# SCH_PBFL.net
KiCad netlist of a schematic drawn in Altium Designer
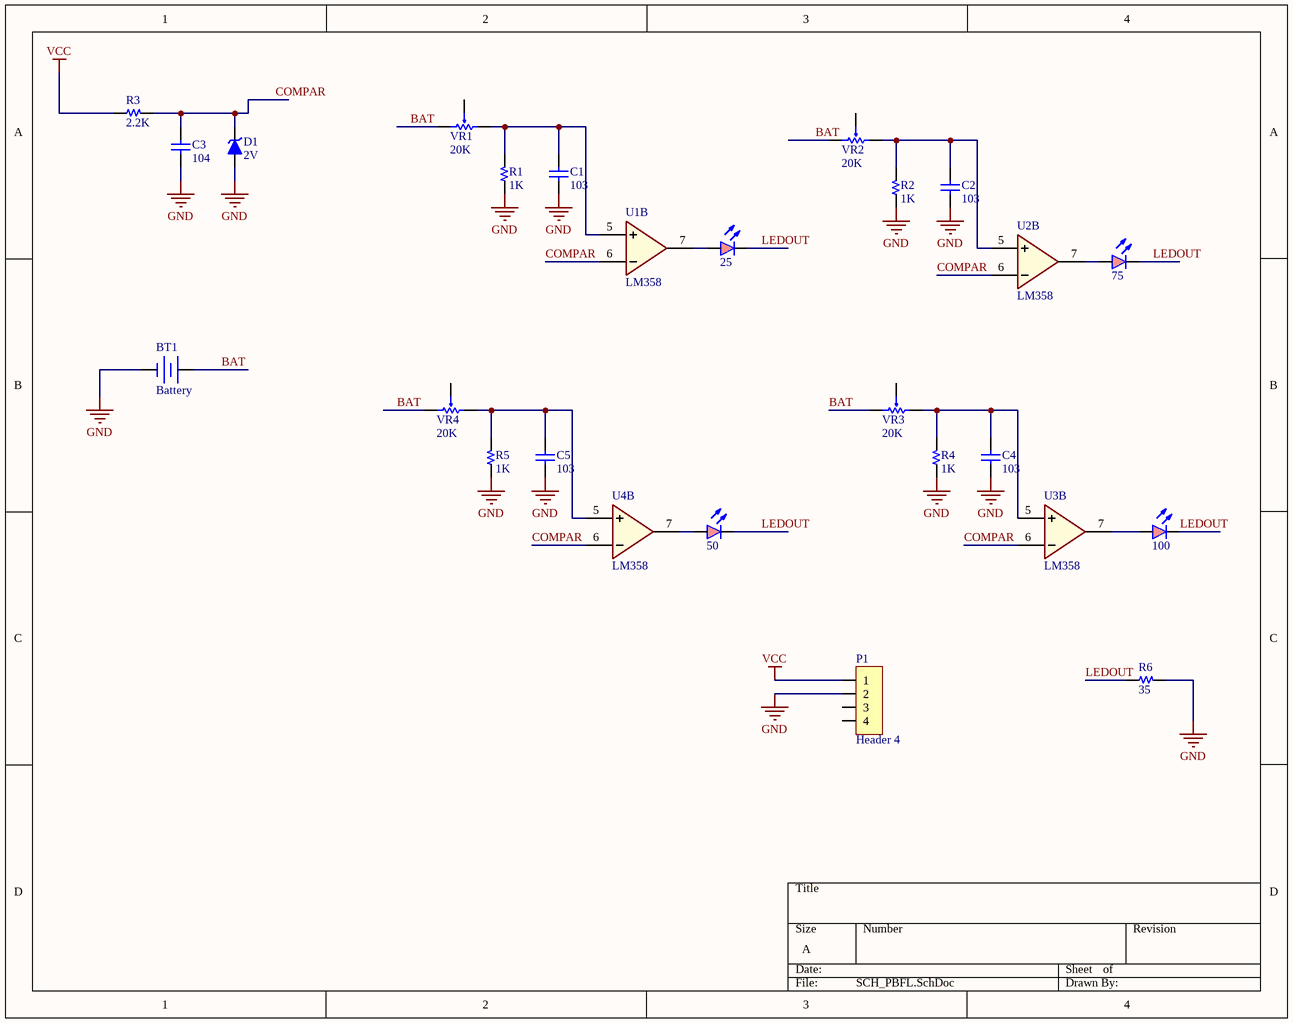
[diagram p0: SCH_PBFL.SchDoc]

(export (version "E")
  (design (tool "Eeschema 10.0.6"))
  (components
    (comp (ref "25")
      (value "LED RED")
      (footprint "LED 10MM - RED")
      (description "Typical LED 3-pin 2-color")
      (libsource (lib "led") (part "LED RED"))
    )
    (comp (ref "50")
      (value "LED RED")
      (footprint "LED 10MM - RED")
      (description "Typical LED 3-pin 2-color")
      (libsource (lib "led") (part "LED RED"))
    )
    (comp (ref "75")
      (value "LED RED")
      (footprint "LED 10MM - RED")
      (description "Typical LED 3-pin 2-color")
      (libsource (lib "led") (part "LED RED"))
    )
    (comp (ref "100")
      (value "LED RED")
      (footprint "LED 10MM - RED")
      (description "Typical LED 3-pin 2-color")
      (libsource (lib "led") (part "LED RED"))
    )
    (comp (ref "BT1")
      (value "Battery")
      (footprint "BB-BAT-18650-x1")
      (libsource (lib "chipfc_libs") (part "Battery"))
    )
    (comp (ref "C1")
      (value "103")
      (footprint "C 0805")
      (description "Capacitor non-pol")
      (libsource (lib "chipfc_libs") (part "Capacitor NP"))
    )
    (comp (ref "C2")
      (value "103")
      (footprint "C 0805")
      (description "Capacitor non-pol")
      (libsource (lib "chipfc_libs") (part "Capacitor NP"))
    )
    (comp (ref "C3")
      (value "104")
      (footprint "C 0805")
      (description "Capacitor non-pol")
      (libsource (lib "chipfc_libs") (part "Capacitor NP"))
    )
    (comp (ref "C4")
      (value "103")
      (footprint "C 0805")
      (description "Capacitor non-pol")
      (libsource (lib "chipfc_libs") (part "Capacitor NP"))
    )
    (comp (ref "C5")
      (value "103")
      (footprint "C 0805")
      (description "Capacitor non-pol")
      (libsource (lib "chipfc_libs") (part "Capacitor NP"))
    )
    (comp (ref "D1")
      (value "2V")
      (footprint "SOD123")
      (description "Zener Diode")
      (libsource (lib "chipfc_libs") (part "Diode Zener"))
    )
    (comp (ref "P1")
      (value "Header 4")
      (footprint "HDR/Header/4/BOX/RED")
      (description "Header, 4-Pin")
      (libsource (lib "connectors") (part "Header 4"))
    )
    (comp (ref "R1")
      (value "1K")
      (footprint "R 0805")
      (description "Resistor")
      (libsource (lib "chipfc_libs") (part "Resistor"))
    )
    (comp (ref "R2")
      (value "1K")
      (footprint "R 0805")
      (description "Resistor")
      (libsource (lib "chipfc_libs") (part "Resistor"))
    )
    (comp (ref "R3")
      (value "2.2K")
      (footprint "R 0805")
      (description "Resistor")
      (libsource (lib "chipfc_libs") (part "Resistor"))
    )
    (comp (ref "R4")
      (value "1K")
      (footprint "R 0805")
      (description "Resistor")
      (libsource (lib "chipfc_libs") (part "Resistor"))
    )
    (comp (ref "R5")
      (value "1K")
      (footprint "R 0805")
      (description "Resistor")
      (libsource (lib "chipfc_libs") (part "Resistor"))
    )
    (comp (ref "R6")
      (value "35")
      (footprint "R 0805")
      (description "Resistor")
      (libsource (lib "chipfc_libs") (part "Resistor"))
    )
    (comp (ref "U1")
      (value "LM358")
      (footprint "SOIC-8")
      (description "Low Power Dual Operational Amplifiers")
      (libsource (lib "chipfc_libs") (part "LM358"))
    )
    (comp (ref "U2")
      (value "LM358")
      (footprint "SOIC-8")
      (description "Low Power Dual Operational Amplifiers")
      (libsource (lib "chipfc_libs") (part "LM358"))
    )
    (comp (ref "U3")
      (value "LM358")
      (footprint "SOIC-8")
      (description "Low Power Dual Operational Amplifiers")
      (libsource (lib "chipfc_libs") (part "LM358"))
    )
    (comp (ref "U4")
      (value "LM358")
      (footprint "SOIC-8")
      (description "Low Power Dual Operational Amplifiers")
      (libsource (lib "chipfc_libs") (part "LM358"))
    )
    (comp (ref "VR1")
      (value "20K")
      (footprint "R VAR E")
      (description "Resistor Variable")
      (libsource (lib "chipfc_libs") (part "Resistor Variable"))
    )
    (comp (ref "VR2")
      (value "20K")
      (footprint "R VAR E")
      (description "Resistor Variable")
      (libsource (lib "chipfc_libs") (part "Resistor Variable"))
    )
    (comp (ref "VR3")
      (value "20K")
      (footprint "R VAR E")
      (description "Resistor Variable")
      (libsource (lib "chipfc_libs") (part "Resistor Variable"))
    )
    (comp (ref "VR4")
      (value "20K")
      (footprint "R VAR E")
      (description "Resistor Variable")
      (libsource (lib "chipfc_libs") (part "Resistor Variable"))
    )
  )
  (nets
    (net (code "1") (name "/BAT") (class "Default")
      (node (ref "BT1") (pin "1") (pinfunction "V+_1") (pintype "passive"))
      (node (ref "VR1") (pin "1") (pinfunction "1_1") (pintype "passive"))
      (node (ref "VR2") (pin "1") (pinfunction "1_1") (pintype "passive"))
      (node (ref "VR3") (pin "1") (pinfunction "1_1") (pintype "passive"))
      (node (ref "VR4") (pin "1") (pinfunction "1_1") (pintype "passive"))
    )
    (net (code "2") (name "/COMPAR") (class "Default")
      (node (ref "C3") (pin "1") (pinfunction "1_1") (pintype "passive"))
      (node (ref "D1") (pin "2") (pinfunction "K_2") (pintype "passive"))
      (node (ref "R3") (pin "2") (pinfunction "2_2") (pintype "passive"))
      (node (ref "U1") (pin "6") (pinfunction "B-_6") (pintype "passive"))
      (node (ref "U2") (pin "6") (pinfunction "B-_6") (pintype "passive"))
      (node (ref "U3") (pin "6") (pinfunction "B-_6") (pintype "passive"))
      (node (ref "U4") (pin "6") (pinfunction "B-_6") (pintype "passive"))
    )
    (net (code "3") (name "/LEDOUT") (class "Default")
      (node (ref "100") (pin "2") (pinfunction "K_2") (pintype "passive"))
      (node (ref "25") (pin "2") (pinfunction "K_2") (pintype "passive"))
      (node (ref "50") (pin "2") (pinfunction "K_2") (pintype "passive"))
      (node (ref "75") (pin "2") (pinfunction "K_2") (pintype "passive"))
      (node (ref "R6") (pin "1") (pinfunction "1_1") (pintype "passive"))
    )
    (net (code "4") (name "GND") (class "Default")
      (node (ref "BT1") (pin "2") (pinfunction "V-_2") (pintype "passive"))
      (node (ref "C1") (pin "2") (pinfunction "2_2") (pintype "passive"))
      (node (ref "C2") (pin "2") (pinfunction "2_2") (pintype "passive"))
      (node (ref "C3") (pin "2") (pinfunction "2_2") (pintype "passive"))
      (node (ref "C4") (pin "2") (pinfunction "2_2") (pintype "passive"))
      (node (ref "C5") (pin "2") (pinfunction "2_2") (pintype "passive"))
      (node (ref "D1") (pin "1") (pinfunction "A_1") (pintype "passive"))
      (node (ref "P1") (pin "2") (pinfunction "2_2") (pintype "passive"))
      (node (ref "R1") (pin "1") (pinfunction "1_1") (pintype "passive"))
      (node (ref "R2") (pin "1") (pinfunction "1_1") (pintype "passive"))
      (node (ref "R4") (pin "1") (pinfunction "1_1") (pintype "passive"))
      (node (ref "R5") (pin "1") (pinfunction "1_1") (pintype "passive"))
      (node (ref "R6") (pin "2") (pinfunction "2_2") (pintype "passive"))
    )
    (net (code "5") (name "Net-(25-A)") (class "Default")
      (node (ref "25") (pin "1") (pinfunction "A_1") (pintype "passive"))
      (node (ref "U1") (pin "7") (pinfunction "OutB_7") (pintype "passive"))
    )
    (net (code "6") (name "Net-(50-A)") (class "Default")
      (node (ref "50") (pin "1") (pinfunction "A_1") (pintype "passive"))
      (node (ref "U4") (pin "7") (pinfunction "OutB_7") (pintype "passive"))
    )
    (net (code "7") (name "Net-(75-A)") (class "Default")
      (node (ref "75") (pin "1") (pinfunction "A_1") (pintype "passive"))
      (node (ref "U2") (pin "7") (pinfunction "OutB_7") (pintype "passive"))
    )
    (net (code "8") (name "Net-(100-A)") (class "Default")
      (node (ref "100") (pin "1") (pinfunction "A_1") (pintype "passive"))
      (node (ref "U3") (pin "7") (pinfunction "OutB_7") (pintype "passive"))
    )
    (net (code "9") (name "Net-(U1B-B+)") (class "Default")
      (node (ref "C1") (pin "1") (pinfunction "1_1") (pintype "passive"))
      (node (ref "R1") (pin "2") (pinfunction "2_2") (pintype "passive"))
      (node (ref "U1") (pin "5") (pinfunction "B+_5") (pintype "passive"))
      (node (ref "VR1") (pin "3") (pinfunction "3_3") (pintype "passive"))
    )
    (net (code "10") (name "Net-(U2B-B+)") (class "Default")
      (node (ref "C2") (pin "1") (pinfunction "1_1") (pintype "passive"))
      (node (ref "R2") (pin "2") (pinfunction "2_2") (pintype "passive"))
      (node (ref "U2") (pin "5") (pinfunction "B+_5") (pintype "passive"))
      (node (ref "VR2") (pin "3") (pinfunction "3_3") (pintype "passive"))
    )
    (net (code "11") (name "Net-(U3B-B+)") (class "Default")
      (node (ref "C4") (pin "1") (pinfunction "1_1") (pintype "passive"))
      (node (ref "R4") (pin "2") (pinfunction "2_2") (pintype "passive"))
      (node (ref "U3") (pin "5") (pinfunction "B+_5") (pintype "passive"))
      (node (ref "VR3") (pin "3") (pinfunction "3_3") (pintype "passive"))
    )
    (net (code "12") (name "Net-(U4B-B+)") (class "Default")
      (node (ref "C5") (pin "1") (pinfunction "1_1") (pintype "passive"))
      (node (ref "R5") (pin "2") (pinfunction "2_2") (pintype "passive"))
      (node (ref "U4") (pin "5") (pinfunction "B+_5") (pintype "passive"))
      (node (ref "VR4") (pin "3") (pinfunction "3_3") (pintype "passive"))
    )
    (net (code "13") (name "VCC") (class "Default")
      (node (ref "P1") (pin "1") (pinfunction "1_1") (pintype "passive"))
      (node (ref "R3") (pin "1") (pinfunction "1_1") (pintype "passive"))
    )
    (net (code "14") (name "unconnected-(P1-Pad3)") (class "Default")
      (node (ref "P1") (pin "3") (pinfunction "3_3") (pintype "passive"))
    )
    (net (code "15") (name "unconnected-(P1-Pad4)") (class "Default")
      (node (ref "P1") (pin "4") (pinfunction "4_4") (pintype "passive"))
    )
    (net (code "16") (name "unconnected-(VR1-Pad2)") (class "Default")
      (node (ref "VR1") (pin "2") (pinfunction "2_2") (pintype "passive"))
    )
    (net (code "17") (name "unconnected-(VR2-Pad2)") (class "Default")
      (node (ref "VR2") (pin "2") (pinfunction "2_2") (pintype "passive"))
    )
    (net (code "18") (name "unconnected-(VR3-Pad2)") (class "Default")
      (node (ref "VR3") (pin "2") (pinfunction "2_2") (pintype "passive"))
    )
    (net (code "19") (name "unconnected-(VR4-Pad2)") (class "Default")
      (node (ref "VR4") (pin "2") (pinfunction "2_2") (pintype "passive"))
    )
  )
)
